# giraffe20_inverted.net
KiCad netlist of a schematic drawn in EAGLE
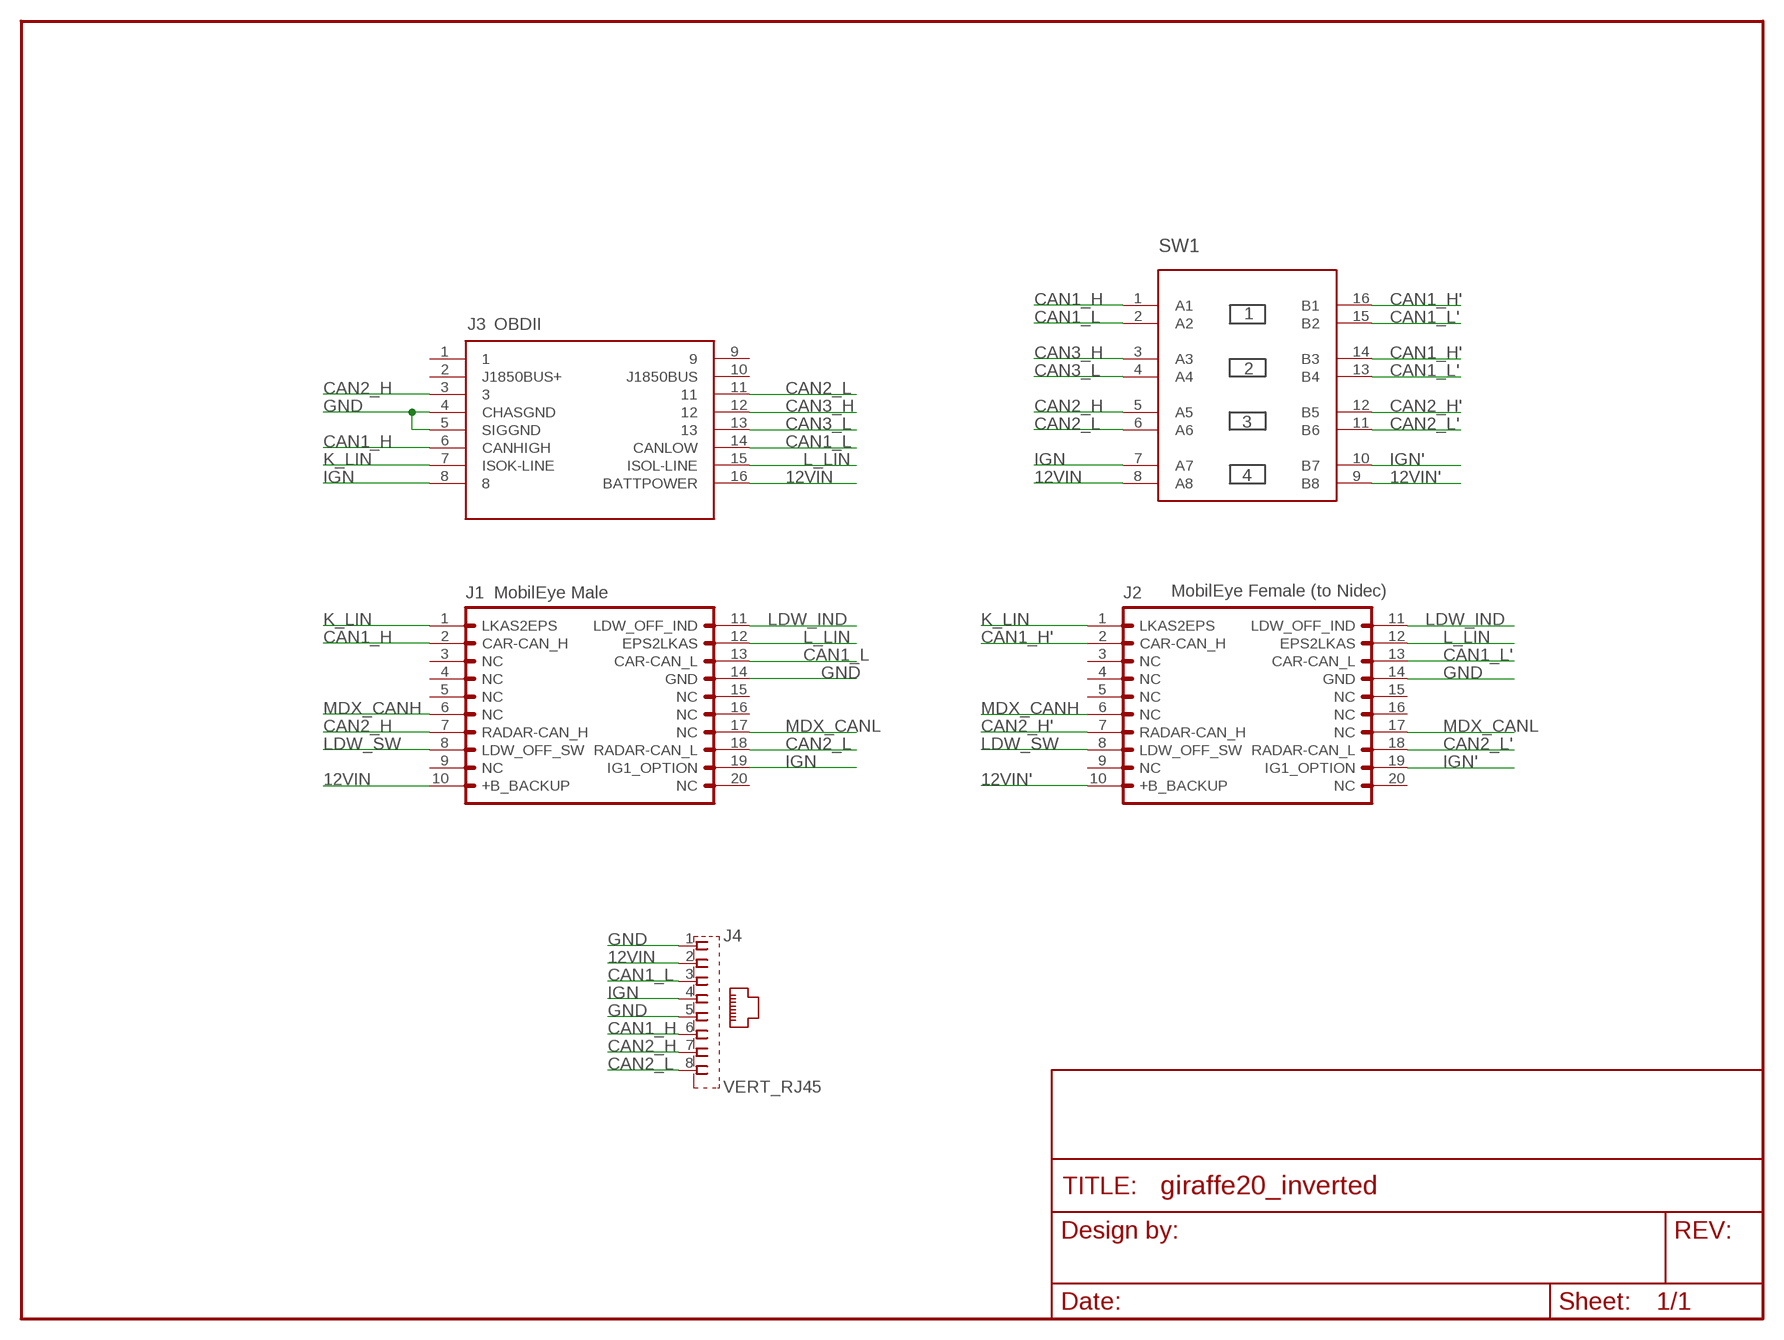
[diagram p0: schematic, sheet 1]

(export (version "E")
  (design (tool "Eeschema 10.0.6"))
  (components
    (comp (ref "FRAME1")
      (value "FRAME-LETTERNO_PACKAGE")
      (footprint "eagle-import:DUMMY")
      (fields (field (name "DESIGNER") "Nobody"))
      (libsource (lib "eagle-import") (part "FRAME-LETTERNO_PACKAGE"))
    )
    (comp (ref "J1")
      (value "MOBILEYERAMALE")
      (footprint "eagle-import:2X10(RA)")
      (libsource (lib "eagle-import") (part "MOBILEYERAMALE"))
    )
    (comp (ref "J2")
      (value "MOBILEYEFEMALE")
      (footprint "eagle-import:2X10(JAE_FEMALE)")
      (libsource (lib "eagle-import") (part "MOBILEYEFEMALE"))
    )
    (comp (ref "J3")
      (value "OBDII-FEMALE-CUT")
      (footprint "eagle-import:OBDII-FEMALE-MIDCUT")
      (libsource (lib "eagle-import") (part "OBDII-FEMALE-CUT"))
    )
    (comp (ref "J4")
      (value "VERT_RJ45")
      (footprint "eagle-import:GLX-S-88M")
      (libsource (lib "eagle-import") (part "VERT_RJ45"))
    )
    (comp (ref "SW1")
      (value "4XDPSTSMT")
      (footprint "eagle-import:4-DPST")
      (libsource (lib "eagle-import") (part "4XDPSTSMT"))
    )
  )
  (nets
    (net (code "1") (name "/12VIN") (class "Default")
      (node (ref "J1") (pin "10") (pinfunction "+B_BACKUP_10") (pintype "bidirectional"))
      (node (ref "J3") (pin "16") (pinfunction "BATTPOWER_16") (pintype "bidirectional"))
      (node (ref "J4") (pin "2") (pinfunction "2_2") (pintype "passive"))
      (node (ref "SW1") (pin "8") (pinfunction "A8_8") (pintype "bidirectional"))
    )
    (net (code "2") (name "/12VIN'") (class "Default")
      (node (ref "J2") (pin "10") (pinfunction "+B_BACKUP_10") (pintype "bidirectional"))
      (node (ref "SW1") (pin "9") (pinfunction "B8_9") (pintype "bidirectional"))
    )
    (net (code "3") (name "/CAN1_H") (class "Default")
      (node (ref "J1") (pin "2") (pinfunction "CAR-CAN_H_2") (pintype "bidirectional"))
      (node (ref "J3") (pin "6") (pinfunction "CANHIGH_6") (pintype "bidirectional"))
      (node (ref "J4") (pin "6") (pinfunction "6_6") (pintype "passive"))
      (node (ref "SW1") (pin "1") (pinfunction "A1_1") (pintype "bidirectional"))
    )
    (net (code "4") (name "/CAN1_H'") (class "Default")
      (node (ref "J2") (pin "2") (pinfunction "CAR-CAN_H_2") (pintype "bidirectional"))
      (node (ref "SW1") (pin "14") (pinfunction "B3_14") (pintype "bidirectional"))
      (node (ref "SW1") (pin "16") (pinfunction "B1_16") (pintype "bidirectional"))
    )
    (net (code "5") (name "/CAN1_L") (class "Default")
      (node (ref "J1") (pin "13") (pinfunction "CAR-CAN_L_13") (pintype "bidirectional"))
      (node (ref "J3") (pin "14") (pinfunction "CANLOW_14") (pintype "bidirectional"))
      (node (ref "J4") (pin "3") (pinfunction "3_3") (pintype "passive"))
      (node (ref "SW1") (pin "2") (pinfunction "A2_2") (pintype "bidirectional"))
    )
    (net (code "6") (name "/CAN1_L'") (class "Default")
      (node (ref "J2") (pin "13") (pinfunction "CAR-CAN_L_13") (pintype "bidirectional"))
      (node (ref "SW1") (pin "13") (pinfunction "B4_13") (pintype "bidirectional"))
      (node (ref "SW1") (pin "15") (pinfunction "B2_15") (pintype "bidirectional"))
    )
    (net (code "7") (name "/CAN2_H") (class "Default")
      (node (ref "J1") (pin "7") (pinfunction "RADAR-CAN_H_7") (pintype "bidirectional"))
      (node (ref "J3") (pin "3") (pinfunction "3_3") (pintype "bidirectional"))
      (node (ref "J4") (pin "7") (pinfunction "7_7") (pintype "passive"))
      (node (ref "SW1") (pin "5") (pinfunction "A5_5") (pintype "bidirectional"))
    )
    (net (code "8") (name "/CAN2_H'") (class "Default")
      (node (ref "J2") (pin "7") (pinfunction "RADAR-CAN_H_7") (pintype "bidirectional"))
      (node (ref "SW1") (pin "12") (pinfunction "B5_12") (pintype "bidirectional"))
    )
    (net (code "9") (name "/CAN2_L") (class "Default")
      (node (ref "J1") (pin "18") (pinfunction "RADAR-CAN_L_18") (pintype "bidirectional"))
      (node (ref "J3") (pin "11") (pinfunction "11_11") (pintype "bidirectional"))
      (node (ref "J4") (pin "8") (pinfunction "8_8") (pintype "passive"))
      (node (ref "SW1") (pin "6") (pinfunction "A6_6") (pintype "bidirectional"))
    )
    (net (code "10") (name "/CAN2_L'") (class "Default")
      (node (ref "J2") (pin "18") (pinfunction "RADAR-CAN_L_18") (pintype "bidirectional"))
      (node (ref "SW1") (pin "11") (pinfunction "B6_11") (pintype "bidirectional"))
    )
    (net (code "11") (name "/CAN3_H") (class "Default")
      (node (ref "J3") (pin "12") (pinfunction "12_12") (pintype "bidirectional"))
      (node (ref "SW1") (pin "3") (pinfunction "A3_3") (pintype "bidirectional"))
    )
    (net (code "12") (name "/CAN3_L") (class "Default")
      (node (ref "J3") (pin "13") (pinfunction "13_13") (pintype "bidirectional"))
      (node (ref "SW1") (pin "4") (pinfunction "A4_4") (pintype "bidirectional"))
    )
    (net (code "13") (name "/GND") (class "Default")
      (node (ref "J1") (pin "14") (pinfunction "GND_14") (pintype "bidirectional"))
      (node (ref "J2") (pin "14") (pinfunction "GND_14") (pintype "bidirectional"))
      (node (ref "J3") (pin "4") (pinfunction "CHASGND_4") (pintype "bidirectional"))
      (node (ref "J3") (pin "5") (pinfunction "SIGGND_5") (pintype "bidirectional"))
      (node (ref "J4") (pin "1") (pinfunction "1_1") (pintype "passive"))
      (node (ref "J4") (pin "5") (pinfunction "5_5") (pintype "passive"))
    )
    (net (code "14") (name "/IGN") (class "Default")
      (node (ref "J1") (pin "19") (pinfunction "IG1_OPTION_19") (pintype "bidirectional"))
      (node (ref "J3") (pin "8") (pinfunction "8_8") (pintype "bidirectional"))
      (node (ref "J4") (pin "4") (pinfunction "4_4") (pintype "passive"))
      (node (ref "SW1") (pin "7") (pinfunction "A7_7") (pintype "bidirectional"))
    )
    (net (code "15") (name "/IGN'") (class "Default")
      (node (ref "J2") (pin "19") (pinfunction "IG1_OPTION_19") (pintype "bidirectional"))
      (node (ref "SW1") (pin "10") (pinfunction "B7_10") (pintype "bidirectional"))
    )
    (net (code "16") (name "/K_LIN") (class "Default")
      (node (ref "J1") (pin "1") (pinfunction "LKAS2EPS_1") (pintype "bidirectional"))
      (node (ref "J2") (pin "1") (pinfunction "LKAS2EPS_1") (pintype "bidirectional"))
      (node (ref "J3") (pin "7") (pinfunction "ISOK-LINE_7") (pintype "bidirectional"))
    )
    (net (code "17") (name "/LDW_IND") (class "Default")
      (node (ref "J1") (pin "11") (pinfunction "LDW_OFF_IND_11") (pintype "bidirectional"))
      (node (ref "J2") (pin "11") (pinfunction "LDW_OFF_IND_11") (pintype "bidirectional"))
    )
    (net (code "18") (name "/LDW_SW") (class "Default")
      (node (ref "J1") (pin "8") (pinfunction "LDW_OFF_SW_8") (pintype "bidirectional"))
      (node (ref "J2") (pin "8") (pinfunction "LDW_OFF_SW_8") (pintype "bidirectional"))
    )
    (net (code "19") (name "/L_LIN") (class "Default")
      (node (ref "J1") (pin "12") (pinfunction "EPS2LKAS_12") (pintype "bidirectional"))
      (node (ref "J2") (pin "12") (pinfunction "EPS2LKAS_12") (pintype "bidirectional"))
      (node (ref "J3") (pin "15") (pinfunction "ISOL-LINE_15") (pintype "bidirectional"))
    )
    (net (code "20") (name "/MDX_CANH") (class "Default")
      (node (ref "J1") (pin "6") (pinfunction "NC_6") (pintype "bidirectional"))
      (node (ref "J2") (pin "6") (pinfunction "NC_6") (pintype "bidirectional"))
    )
    (net (code "21") (name "/MDX_CANL") (class "Default")
      (node (ref "J1") (pin "17") (pinfunction "NC_17") (pintype "bidirectional"))
      (node (ref "J2") (pin "17") (pinfunction "NC_17") (pintype "bidirectional"))
    )
    (net (code "22") (name "unconnected-(J1-NC-Pad3)") (class "Default")
      (node (ref "J1") (pin "3") (pinfunction "NC_3") (pintype "bidirectional"))
    )
    (net (code "23") (name "unconnected-(J1-NC-Pad4)") (class "Default")
      (node (ref "J1") (pin "4") (pinfunction "NC_4") (pintype "bidirectional"))
    )
    (net (code "24") (name "unconnected-(J1-NC-Pad5)") (class "Default")
      (node (ref "J1") (pin "5") (pinfunction "NC_5") (pintype "bidirectional"))
    )
    (net (code "25") (name "unconnected-(J1-NC-Pad9)") (class "Default")
      (node (ref "J1") (pin "9") (pinfunction "NC_9") (pintype "bidirectional"))
    )
    (net (code "26") (name "unconnected-(J1-NC-Pad15)") (class "Default")
      (node (ref "J1") (pin "15") (pinfunction "NC_15") (pintype "bidirectional"))
    )
    (net (code "27") (name "unconnected-(J1-NC-Pad16)") (class "Default")
      (node (ref "J1") (pin "16") (pinfunction "NC_16") (pintype "bidirectional"))
    )
    (net (code "28") (name "unconnected-(J1-NC-Pad20)") (class "Default")
      (node (ref "J1") (pin "20") (pinfunction "NC_20") (pintype "bidirectional"))
    )
    (net (code "29") (name "unconnected-(J2-NC-Pad3)") (class "Default")
      (node (ref "J2") (pin "3") (pinfunction "NC_3") (pintype "bidirectional"))
    )
    (net (code "30") (name "unconnected-(J2-NC-Pad4)") (class "Default")
      (node (ref "J2") (pin "4") (pinfunction "NC_4") (pintype "bidirectional"))
    )
    (net (code "31") (name "unconnected-(J2-NC-Pad5)") (class "Default")
      (node (ref "J2") (pin "5") (pinfunction "NC_5") (pintype "bidirectional"))
    )
    (net (code "32") (name "unconnected-(J2-NC-Pad9)") (class "Default")
      (node (ref "J2") (pin "9") (pinfunction "NC_9") (pintype "bidirectional"))
    )
    (net (code "33") (name "unconnected-(J2-NC-Pad15)") (class "Default")
      (node (ref "J2") (pin "15") (pinfunction "NC_15") (pintype "bidirectional"))
    )
    (net (code "34") (name "unconnected-(J2-NC-Pad16)") (class "Default")
      (node (ref "J2") (pin "16") (pinfunction "NC_16") (pintype "bidirectional"))
    )
    (net (code "35") (name "unconnected-(J2-NC-Pad20)") (class "Default")
      (node (ref "J2") (pin "20") (pinfunction "NC_20") (pintype "bidirectional"))
    )
    (net (code "36") (name "unconnected-(J3-J1850BUS+-Pad2)") (class "Default")
      (node (ref "J3") (pin "2") (pinfunction "J1850BUS+_2") (pintype "bidirectional"))
    )
    (net (code "37") (name "unconnected-(J3-J1850BUS-Pad10)") (class "Default")
      (node (ref "J3") (pin "10") (pinfunction "J1850BUS_10") (pintype "bidirectional"))
    )
    (net (code "38") (name "unconnected-(J3-Pad1)") (class "Default")
      (node (ref "J3") (pin "1") (pinfunction "1_1") (pintype "bidirectional"))
    )
    (net (code "39") (name "unconnected-(J3-Pad9)") (class "Default")
      (node (ref "J3") (pin "9") (pinfunction "9_9") (pintype "bidirectional"))
    )
  )
)
